# PCM-DAC.net
KiCad netlist of a schematic drawn in EAGLE
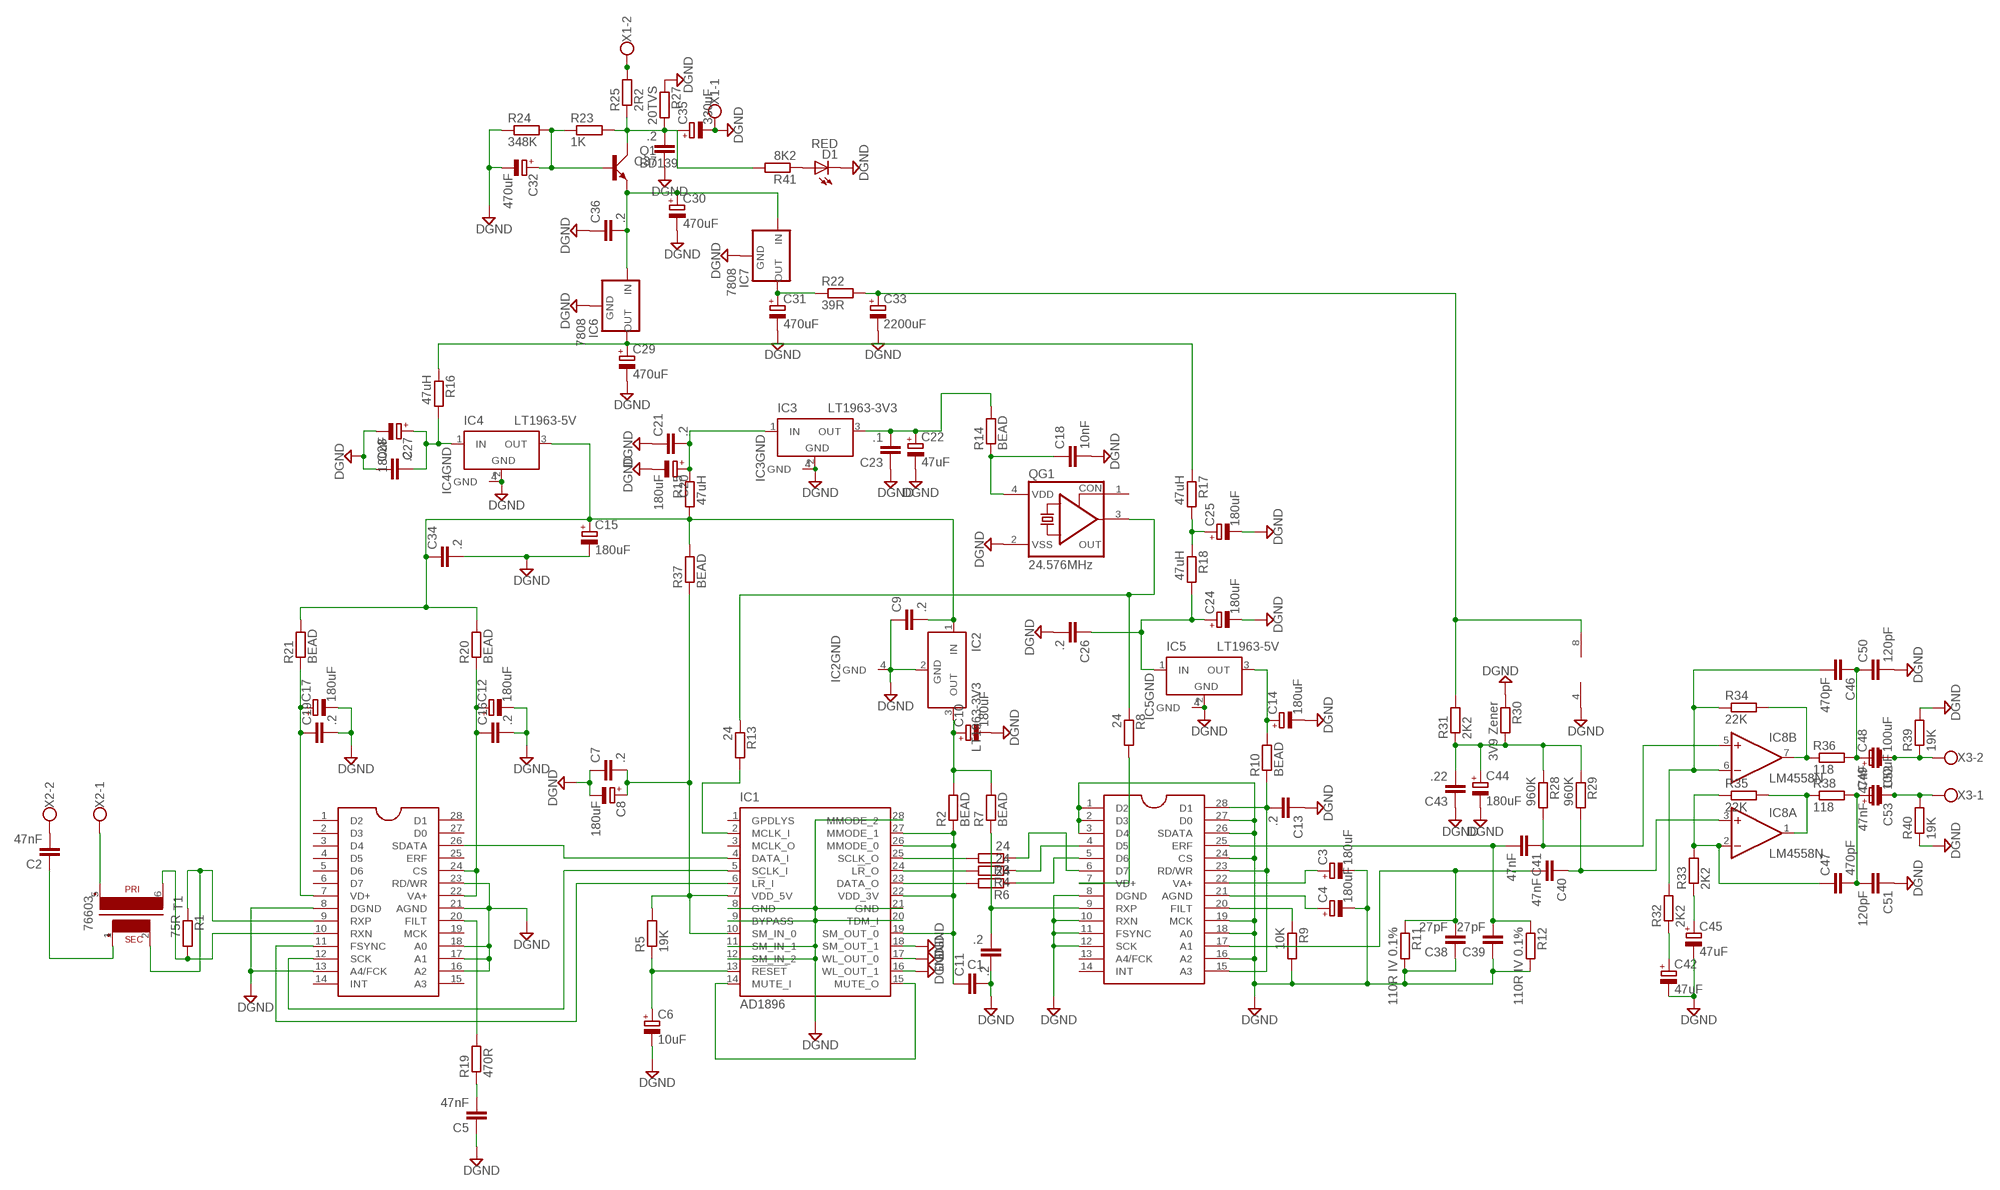
[diagram p0: schematic, sheet 1]

(export (version "E")
  (design (tool "Eeschema 10.0.6"))
  (components
    (comp (ref "C1")
      (value ".2")
      (footprint "eagle-import:C1210K")
      (libsource (lib "eagle-import") (part "C-EUC1210K"))
    )
    (comp (ref "C2")
      (value "47nF")
      (footprint "eagle-import:C050-075X075")
      (libsource (lib "eagle-import") (part "C-EU050-075X075"))
    )
    (comp (ref "C3")
      (value "180uF")
      (footprint "eagle-import:E3,5-8")
      (libsource (lib "eagle-import") (part "CPOL-EUE3.5-8"))
    )
    (comp (ref "C4")
      (value "180uF")
      (footprint "eagle-import:E3,5-8")
      (libsource (lib "eagle-import") (part "CPOL-EUE3.5-8"))
    )
    (comp (ref "C5")
      (value "47nF")
      (footprint "eagle-import:C050-075X075")
      (libsource (lib "eagle-import") (part "C-EU050-075X075"))
    )
    (comp (ref "C6")
      (value "10uF")
      (footprint "eagle-import:E2,5-7")
      (libsource (lib "eagle-import") (part "CPOL-EUE2.5-7"))
    )
    (comp (ref "C7")
      (value ".2")
      (footprint "eagle-import:C1210K")
      (libsource (lib "eagle-import") (part "C-EUC1210K"))
    )
    (comp (ref "C8")
      (value "180uF")
      (footprint "eagle-import:E3,5-8")
      (libsource (lib "eagle-import") (part "CPOL-EUE3.5-8"))
    )
    (comp (ref "C9")
      (value ".2")
      (footprint "eagle-import:C1210K")
      (libsource (lib "eagle-import") (part "C-EUC1210K"))
    )
    (comp (ref "C10")
      (value "180uF")
      (footprint "eagle-import:E3,5-8")
      (libsource (lib "eagle-import") (part "CPOL-EUE3.5-8"))
    )
    (comp (ref "C11")
      (value ".2")
      (footprint "eagle-import:C1210K")
      (libsource (lib "eagle-import") (part "C-EUC1210K"))
    )
    (comp (ref "C12")
      (value "180uF")
      (footprint "eagle-import:E3,5-8")
      (libsource (lib "eagle-import") (part "CPOL-EUE3.5-8"))
    )
    (comp (ref "C13")
      (value ".2")
      (footprint "eagle-import:C1210K")
      (libsource (lib "eagle-import") (part "C-EUC1210K"))
    )
    (comp (ref "C14")
      (value "180uF")
      (footprint "eagle-import:E3,5-8")
      (libsource (lib "eagle-import") (part "CPOL-EUE3.5-8"))
    )
    (comp (ref "C15")
      (value "180uF")
      (footprint "eagle-import:E3,5-8")
      (libsource (lib "eagle-import") (part "CPOL-EUE3.5-8"))
    )
    (comp (ref "C16")
      (value ".2")
      (footprint "eagle-import:C1210K")
      (libsource (lib "eagle-import") (part "C-EUC1210K"))
    )
    (comp (ref "C17")
      (value "180uF")
      (footprint "eagle-import:E3,5-8")
      (libsource (lib "eagle-import") (part "CPOL-EUE3.5-8"))
    )
    (comp (ref "C18")
      (value "10nF")
      (footprint "eagle-import:C1210K")
      (libsource (lib "eagle-import") (part "C-EUC1210K"))
    )
    (comp (ref "C19")
      (value ".2")
      (footprint "eagle-import:C1210K")
      (libsource (lib "eagle-import") (part "C-EUC1210K"))
    )
    (comp (ref "C20")
      (value "180uF")
      (footprint "eagle-import:E3,5-8")
      (libsource (lib "eagle-import") (part "CPOL-EUE3.5-8"))
    )
    (comp (ref "C21")
      (value ".2")
      (footprint "eagle-import:C1210K")
      (libsource (lib "eagle-import") (part "C-EUC1210K"))
    )
    (comp (ref "C22")
      (value "47uF")
      (footprint "eagle-import:E3,5-8")
      (libsource (lib "eagle-import") (part "CPOL-EUE3.5-8"))
    )
    (comp (ref "C23")
      (value ".1")
      (footprint "eagle-import:C1210K")
      (libsource (lib "eagle-import") (part "C-EUC1210K"))
    )
    (comp (ref "C24")
      (value "180uF")
      (footprint "eagle-import:E3,5-8")
      (libsource (lib "eagle-import") (part "CPOL-EUE3.5-8"))
    )
    (comp (ref "C25")
      (value "180uF")
      (footprint "eagle-import:E3,5-8")
      (libsource (lib "eagle-import") (part "CPOL-EUE3.5-8"))
    )
    (comp (ref "C26")
      (value ".2")
      (footprint "eagle-import:C1210K")
      (libsource (lib "eagle-import") (part "C-EUC1210K"))
    )
    (comp (ref "C27")
      (value "180uF")
      (footprint "eagle-import:E3,5-8")
      (libsource (lib "eagle-import") (part "CPOL-EUE3.5-8"))
    )
    (comp (ref "C28")
      (value ".2")
      (footprint "eagle-import:C1210K")
      (libsource (lib "eagle-import") (part "C-EUC1210K"))
    )
    (comp (ref "C29")
      (value "470uF")
      (footprint "eagle-import:E5-10,5")
      (libsource (lib "eagle-import") (part "CPOL-EUE5-10.5"))
    )
    (comp (ref "C30")
      (value "470uF")
      (footprint "eagle-import:E5-10,5")
      (libsource (lib "eagle-import") (part "CPOL-EUE5-10.5"))
    )
    (comp (ref "C31")
      (value "470uF")
      (footprint "eagle-import:E5-10,5")
      (libsource (lib "eagle-import") (part "CPOL-EUE5-10.5"))
    )
    (comp (ref "C32")
      (value "470uF")
      (footprint "eagle-import:E5-10,5")
      (libsource (lib "eagle-import") (part "CPOL-EUE5-10.5"))
    )
    (comp (ref "C33")
      (value "2200uF")
      (footprint "eagle-import:E7,5-16")
      (libsource (lib "eagle-import") (part "CPOL-EUE7.5-16"))
    )
    (comp (ref "C34")
      (value ".2")
      (footprint "eagle-import:C1210K")
      (libsource (lib "eagle-import") (part "C-EUC1210K"))
    )
    (comp (ref "C35")
      (value "330uF")
      (footprint "eagle-import:E7,5-16")
      (libsource (lib "eagle-import") (part "CPOL-EUE7.5-16"))
    )
    (comp (ref "C36")
      (value ".2")
      (footprint "eagle-import:C1210K")
      (libsource (lib "eagle-import") (part "C-EUC1210K"))
    )
    (comp (ref "C37")
      (value ".2")
      (footprint "eagle-import:C1210K")
      (libsource (lib "eagle-import") (part "C-EUC1210K"))
    )
    (comp (ref "C38")
      (value "27pF")
      (footprint "eagle-import:C1210K")
      (libsource (lib "eagle-import") (part "C-EUC1210K"))
    )
    (comp (ref "C39")
      (value "27pF")
      (footprint "eagle-import:C1210K")
      (libsource (lib "eagle-import") (part "C-EUC1210K"))
    )
    (comp (ref "C40")
      (value "47nF")
      (footprint "eagle-import:C050-075X075")
      (libsource (lib "eagle-import") (part "C-EU050-075X075"))
    )
    (comp (ref "C41")
      (value "47nF")
      (footprint "eagle-import:C050-075X075")
      (libsource (lib "eagle-import") (part "C-EU050-075X075"))
    )
    (comp (ref "C42")
      (value "47uF")
      (footprint "eagle-import:E3,5-8")
      (libsource (lib "eagle-import") (part "CPOL-EUE3.5-8"))
    )
    (comp (ref "C43")
      (value ".22")
      (footprint "eagle-import:C1210K")
      (libsource (lib "eagle-import") (part "C-EUC1210K"))
    )
    (comp (ref "C44")
      (value "180uF")
      (footprint "eagle-import:E5-10,5")
      (libsource (lib "eagle-import") (part "CPOL-EUE5-10.5"))
    )
    (comp (ref "C45")
      (value "47uF")
      (footprint "eagle-import:E3,5-8")
      (libsource (lib "eagle-import") (part "CPOL-EUE3.5-8"))
    )
    (comp (ref "C46")
      (value "470pF")
      (footprint "eagle-import:C1210K")
      (libsource (lib "eagle-import") (part "C-EUC1210K"))
    )
    (comp (ref "C47")
      (value "470pF")
      (footprint "eagle-import:C1210K")
      (libsource (lib "eagle-import") (part "C-EUC1210K"))
    )
    (comp (ref "C48")
      (value "100uF")
      (footprint "eagle-import:E5-10,5")
      (libsource (lib "eagle-import") (part "CPOL-EUE5-10.5"))
    )
    (comp (ref "C49")
      (value "100uF")
      (footprint "eagle-import:E5-10,5")
      (libsource (lib "eagle-import") (part "CPOL-EUE5-10.5"))
    )
    (comp (ref "C50")
      (value "120pF")
      (footprint "eagle-import:C1210K")
      (libsource (lib "eagle-import") (part "C-EUC1210K"))
    )
    (comp (ref "C51")
      (value "120pF")
      (footprint "eagle-import:C1210K")
      (libsource (lib "eagle-import") (part "C-EUC1210K"))
    )
    (comp (ref "C52")
      (value "47nF")
      (footprint "eagle-import:C050-075X075")
      (libsource (lib "eagle-import") (part "C-EU050-075X075"))
    )
    (comp (ref "C53")
      (value "47nF")
      (footprint "eagle-import:C050-075X075")
      (libsource (lib "eagle-import") (part "C-EU050-075X075"))
    )
    (comp (ref "D1")
      (value "RED")
      (footprint "eagle-import:SFH482")
      (libsource (lib "eagle-import") (part "SFH482"))
    )
    (comp (ref "IC1")
      (value "AD1896")
      (footprint "eagle-import:DIL28-6")
      (libsource (lib "eagle-import") (part "AD1896JN"))
    )
    (comp (ref "IC2")
      (value "LT1963-3V3")
      (footprint "eagle-import:SOT223")
      (libsource (lib "eagle-import") (part "LT1129CST5"))
    )
    (comp (ref "IC3")
      (value "LT1963-3V3")
      (footprint "eagle-import:SOT223")
      (libsource (lib "eagle-import") (part "LT1129CST5"))
    )
    (comp (ref "IC4")
      (value "LT1963-5V")
      (footprint "eagle-import:SOT223")
      (libsource (lib "eagle-import") (part "LT1129CST5"))
    )
    (comp (ref "IC5")
      (value "LT1963-5V")
      (footprint "eagle-import:SOT223")
      (libsource (lib "eagle-import") (part "LT1129CST5"))
    )
    (comp (ref "IC6")
      (value "7808")
      (footprint "eagle-import:78XXL")
      (libsource (lib "eagle-import") (part "78XXL"))
    )
    (comp (ref "IC7")
      (value "7808")
      (footprint "eagle-import:78XXL")
      (libsource (lib "eagle-import") (part "78XXL"))
    )
    (comp (ref "IC8")
      (value "LM4558N")
      (footprint "eagle-import:DIL08")
      (libsource (lib "eagle-import") (part "4558NLM"))
    )
    (comp (ref "Q1")
      (value "BD139")
      (footprint "eagle-import:TO126AV")
      (libsource (lib "eagle-import") (part "BD139"))
    )
    (comp (ref "QG1")
      (value "24.576MHz")
      (footprint "eagle-import:1100S")
      (libsource (lib "eagle-import") (part "CRYSTAL_RES-1100S"))
    )
    (comp (ref "R1")
      (value "75R")
      (footprint "eagle-import:0309_12")
      (libsource (lib "eagle-import") (part "R-EU_0309/12"))
    )
    (comp (ref "R2")
      (value "BEAD")
      (footprint "eagle-import:R1210")
      (libsource (lib "eagle-import") (part "R-EU_R1210"))
    )
    (comp (ref "R3")
      (value "24")
      (footprint "eagle-import:R1210")
      (libsource (lib "eagle-import") (part "R-EU_R1210"))
    )
    (comp (ref "R4")
      (value "24")
      (footprint "eagle-import:R1210")
      (libsource (lib "eagle-import") (part "R-EU_R1210"))
    )
    (comp (ref "R5")
      (value "19K")
      (footprint "eagle-import:0204_7")
      (libsource (lib "eagle-import") (part "R-EU_0204/7"))
    )
    (comp (ref "R6")
      (value "24")
      (footprint "eagle-import:R1210")
      (libsource (lib "eagle-import") (part "R-EU_R1210"))
    )
    (comp (ref "R7")
      (value "BEAD")
      (footprint "eagle-import:R1210")
      (libsource (lib "eagle-import") (part "R-EU_R1210"))
    )
    (comp (ref "R8")
      (value "24")
      (footprint "eagle-import:R1210")
      (libsource (lib "eagle-import") (part "R-EU_R1210"))
    )
    (comp (ref "R9")
      (value "10K")
      (footprint "eagle-import:R1210")
      (libsource (lib "eagle-import") (part "R-EU_R1210"))
    )
    (comp (ref "R10")
      (value "BEAD")
      (footprint "eagle-import:R1210")
      (libsource (lib "eagle-import") (part "R-EU_R1210"))
    )
    (comp (ref "R11")
      (value "110R IV 0.1%")
      (footprint "eagle-import:0309_12")
      (libsource (lib "eagle-import") (part "R-EU_0309/12"))
    )
    (comp (ref "R12")
      (value "110R IV 0.1%")
      (footprint "eagle-import:0309_12")
      (libsource (lib "eagle-import") (part "R-EU_0309/12"))
    )
    (comp (ref "R13")
      (value "24")
      (footprint "eagle-import:R1210")
      (libsource (lib "eagle-import") (part "R-EU_R1210"))
    )
    (comp (ref "R14")
      (value "BEAD")
      (footprint "eagle-import:R1210")
      (libsource (lib "eagle-import") (part "R-EU_R1210"))
    )
    (comp (ref "R15")
      (value "47uH")
      (footprint "eagle-import:0309_12")
      (libsource (lib "eagle-import") (part "R-EU_0309/12"))
    )
    (comp (ref "R16")
      (value "47uH")
      (footprint "eagle-import:0309_12")
      (libsource (lib "eagle-import") (part "R-EU_0309/12"))
    )
    (comp (ref "R17")
      (value "47uH")
      (footprint "eagle-import:0309_12")
      (libsource (lib "eagle-import") (part "R-EU_0309/12"))
    )
    (comp (ref "R18")
      (value "47uH")
      (footprint "eagle-import:0309_12")
      (libsource (lib "eagle-import") (part "R-EU_0309/12"))
    )
    (comp (ref "R19")
      (value "470R")
      (footprint "eagle-import:0204_7")
      (libsource (lib "eagle-import") (part "R-EU_0204/7"))
    )
    (comp (ref "R20")
      (value "BEAD")
      (footprint "eagle-import:R1210")
      (libsource (lib "eagle-import") (part "R-EU_R1210"))
    )
    (comp (ref "R21")
      (value "BEAD")
      (footprint "eagle-import:R1210")
      (libsource (lib "eagle-import") (part "R-EU_R1210"))
    )
    (comp (ref "R22")
      (value "39R")
      (footprint "eagle-import:0309_12")
      (libsource (lib "eagle-import") (part "R-EU_0309/12"))
    )
    (comp (ref "R23")
      (value "1K")
      (footprint "eagle-import:R1210")
      (libsource (lib "eagle-import") (part "R-EU_R1210"))
    )
    (comp (ref "R24")
      (value "348K")
      (footprint "eagle-import:R1210")
      (libsource (lib "eagle-import") (part "R-EU_R1210"))
    )
    (comp (ref "R25")
      (value "2R2")
      (footprint "eagle-import:0309_12")
      (libsource (lib "eagle-import") (part "R-EU_0309/12"))
    )
    (comp (ref "R27")
      (value "20TVS")
      (footprint "eagle-import:R5025")
      (libsource (lib "eagle-import") (part "R-EU_R5025"))
    )
    (comp (ref "R28")
      (value "960K")
      (footprint "eagle-import:0309_12")
      (libsource (lib "eagle-import") (part "R-EU_0309/12"))
    )
    (comp (ref "R29")
      (value "960K")
      (footprint "eagle-import:0309_12")
      (libsource (lib "eagle-import") (part "R-EU_0309/12"))
    )
    (comp (ref "R30")
      (value "3V9 Zener")
      (footprint "eagle-import:R1210")
      (libsource (lib "eagle-import") (part "R-EU_R1210"))
    )
    (comp (ref "R31")
      (value "2K2")
      (footprint "eagle-import:R1210")
      (libsource (lib "eagle-import") (part "R-EU_R1210"))
    )
    (comp (ref "R32")
      (value "2K2")
      (footprint "eagle-import:R1210")
      (libsource (lib "eagle-import") (part "R-EU_R1210"))
    )
    (comp (ref "R33")
      (value "2K2")
      (footprint "eagle-import:R1210")
      (libsource (lib "eagle-import") (part "R-EU_R1210"))
    )
    (comp (ref "R34")
      (value "22K")
      (footprint "eagle-import:0309_12")
      (libsource (lib "eagle-import") (part "R-EU_0309/12"))
    )
    (comp (ref "R35")
      (value "22K")
      (footprint "eagle-import:0309_12")
      (libsource (lib "eagle-import") (part "R-EU_0309/12"))
    )
    (comp (ref "R36")
      (value "118")
      (footprint "eagle-import:0309_12")
      (libsource (lib "eagle-import") (part "R-EU_0309/12"))
    )
    (comp (ref "R37")
      (value "BEAD")
      (footprint "eagle-import:R1210")
      (libsource (lib "eagle-import") (part "R-EU_R1210"))
    )
    (comp (ref "R38")
      (value "118")
      (footprint "eagle-import:0309_12")
      (libsource (lib "eagle-import") (part "R-EU_0309/12"))
    )
    (comp (ref "R39")
      (value "19K")
      (footprint "eagle-import:0309_12")
      (libsource (lib "eagle-import") (part "R-EU_0309/12"))
    )
    (comp (ref "R40")
      (value "19K")
      (footprint "eagle-import:0309_12")
      (libsource (lib "eagle-import") (part "R-EU_0309/12"))
    )
    (comp (ref "R41")
      (value "8K2")
      (footprint "eagle-import:R1210")
      (libsource (lib "eagle-import") (part "R-EU_R1210"))
    )
    (comp (ref "T1")
      (value "76603")
      (footprint "eagle-import:766-4")
      (libsource (lib "eagle-import") (part "76603"))
    )
    (comp (ref "U$1")
      (value "CS8412")
      (footprint "eagle-import:DIL28")
      (libsource (lib "eagle-import") (part "CS8412DIP"))
    )
    (comp (ref "U$2")
      (value "PCM1794A")
      (footprint "eagle-import:DIL28")
      (libsource (lib "eagle-import") (part "CS8412DIP"))
    )
    (comp (ref "X1")
      (value "W237-02P")
      (footprint "eagle-import:W237-132")
      (libsource (lib "eagle-import") (part "W237-02P"))
    )
    (comp (ref "X2")
      (value "W237-02P")
      (footprint "eagle-import:W237-132")
      (libsource (lib "eagle-import") (part "W237-02P"))
    )
    (comp (ref "X3")
      (value "W237-02P")
      (footprint "eagle-import:W237-132")
      (libsource (lib "eagle-import") (part "W237-02P"))
    )
  )
  (nets
    (net (code "1") (name "DGND") (class "Default")
      (node (ref "C1") (pin "1") (pinfunction "1_1") (pintype "passive"))
      (node (ref "C10") (pin "-") (pinfunction "-_-") (pintype "passive"))
      (node (ref "C11") (pin "2") (pinfunction "2_2") (pintype "passive"))
      (node (ref "C12") (pin "-") (pinfunction "-_-") (pintype "passive"))
      (node (ref "C13") (pin "1") (pinfunction "1_1") (pintype "passive"))
      (node (ref "C14") (pin "-") (pinfunction "-_-") (pintype "passive"))
      (node (ref "C15") (pin "-") (pinfunction "-_-") (pintype "passive"))
      (node (ref "C16") (pin "2") (pinfunction "2_2") (pintype "passive"))
      (node (ref "C17") (pin "-") (pinfunction "-_-") (pintype "passive"))
      (node (ref "C18") (pin "2") (pinfunction "2_2") (pintype "passive"))
      (node (ref "C19") (pin "2") (pinfunction "2_2") (pintype "passive"))
      (node (ref "C20") (pin "-") (pinfunction "-_-") (pintype "passive"))
      (node (ref "C21") (pin "1") (pinfunction "1_1") (pintype "passive"))
      (node (ref "C22") (pin "-") (pinfunction "-_-") (pintype "passive"))
      (node (ref "C23") (pin "1") (pinfunction "1_1") (pintype "passive"))
      (node (ref "C24") (pin "-") (pinfunction "-_-") (pintype "passive"))
      (node (ref "C25") (pin "-") (pinfunction "-_-") (pintype "passive"))
      (node (ref "C26") (pin "2") (pinfunction "2_2") (pintype "passive"))
      (node (ref "C27") (pin "-") (pinfunction "-_-") (pintype "passive"))
      (node (ref "C28") (pin "1") (pinfunction "1_1") (pintype "passive"))
      (node (ref "C29") (pin "-") (pinfunction "-_-") (pintype "passive"))
      (node (ref "C3") (pin "-") (pinfunction "-_-") (pintype "passive"))
      (node (ref "C30") (pin "-") (pinfunction "-_-") (pintype "passive"))
      (node (ref "C31") (pin "-") (pinfunction "-_-") (pintype "passive"))
      (node (ref "C32") (pin "-") (pinfunction "-_-") (pintype "passive"))
      (node (ref "C33") (pin "-") (pinfunction "-_-") (pintype "passive"))
      (node (ref "C34") (pin "2") (pinfunction "2_2") (pintype "passive"))
      (node (ref "C35") (pin "-") (pinfunction "-_-") (pintype "passive"))
      (node (ref "C36") (pin "1") (pinfunction "1_1") (pintype "passive"))
      (node (ref "C37") (pin "1") (pinfunction "1_1") (pintype "passive"))
      (node (ref "C38") (pin "1") (pinfunction "1_1") (pintype "passive"))
      (node (ref "C39") (pin "1") (pinfunction "1_1") (pintype "passive"))
      (node (ref "C4") (pin "-") (pinfunction "-_-") (pintype "passive"))
      (node (ref "C42") (pin "-") (pinfunction "-_-") (pintype "passive"))
      (node (ref "C43") (pin "1") (pinfunction "1_1") (pintype "passive"))
      (node (ref "C44") (pin "-") (pinfunction "-_-") (pintype "passive"))
      (node (ref "C45") (pin "-") (pinfunction "-_-") (pintype "passive"))
      (node (ref "C5") (pin "1") (pinfunction "1_1") (pintype "passive"))
      (node (ref "C50") (pin "2") (pinfunction "2_2") (pintype "passive"))
      (node (ref "C51") (pin "1") (pinfunction "1_1") (pintype "passive"))
      (node (ref "C6") (pin "-") (pinfunction "-_-") (pintype "passive"))
      (node (ref "C7") (pin "1") (pinfunction "1_1") (pintype "passive"))
      (node (ref "C8") (pin "-") (pinfunction "-_-") (pintype "passive"))
      (node (ref "C9") (pin "1") (pinfunction "1_1") (pintype "passive"))
      (node (ref "D1") (pin "K") (pinfunction "C_K") (pintype "passive"))
      (node (ref "IC1") (pin "11") (pinfunction "SM_IN_1_11") (pintype "input"))
      (node (ref "IC1") (pin "12") (pinfunction "SM_IN_2_12") (pintype "input"))
      (node (ref "IC1") (pin "16") (pinfunction "WL_OUT_1_16") (pintype "output"))
      (node (ref "IC1") (pin "17") (pinfunction "WL_OUT_0_17") (pintype "output"))
      (node (ref "IC1") (pin "18") (pinfunction "SM_OUT_1_18") (pintype "output"))
      (node (ref "IC1") (pin "20") (pinfunction "TDM_I_20") (pintype "input"))
      (node (ref "IC1") (pin "21") (pinfunction "GND_21") (pintype "power_in"))
      (node (ref "IC1") (pin "28") (pinfunction "MMODE_2_28") (pintype "input"))
      (node (ref "IC1") (pin "8") (pinfunction "GND_8") (pintype "power_in"))
      (node (ref "IC1") (pin "9") (pinfunction "BYPASS_9") (pintype "bidirectional"))
      (node (ref "IC2") (pin "2") (pinfunction "GND_2") (pintype "power_in"))
      (node (ref "IC2") (pin "4") (pinfunction "GND_4") (pintype "power_in"))
      (node (ref "IC3") (pin "2") (pinfunction "GND_2") (pintype "power_in"))
      (node (ref "IC3") (pin "4") (pinfunction "GND_4") (pintype "power_in"))
      (node (ref "IC4") (pin "2") (pinfunction "GND_2") (pintype "power_in"))
      (node (ref "IC4") (pin "4") (pinfunction "GND_4") (pintype "power_in"))
      (node (ref "IC5") (pin "2") (pinfunction "GND_2") (pintype "power_in"))
      (node (ref "IC5") (pin "4") (pinfunction "GND_4") (pintype "power_in"))
      (node (ref "IC6") (pin "GND") (pinfunction "GND_GND") (pintype "input"))
      (node (ref "IC7") (pin "GND") (pinfunction "GND_GND") (pintype "input"))
      (node (ref "IC8") (pin "4") (pinfunction "V-_4") (pintype "power_in"))
      (node (ref "QG1") (pin "2") (pinfunction "VSS_2") (pintype "power_in"))
      (node (ref "R11") (pin "2") (pinfunction "2_2") (pintype "passive"))
      (node (ref "R12") (pin "2") (pinfunction "2_2") (pintype "passive"))
      (node (ref "R24") (pin "1") (pinfunction "1_1") (pintype "passive"))
      (node (ref "R27") (pin "1") (pinfunction "1_1") (pintype "passive"))
      (node (ref "R30") (pin "1") (pinfunction "1_1") (pintype "passive"))
      (node (ref "R39") (pin "2") (pinfunction "2_2") (pintype "passive"))
      (node (ref "R40") (pin "1") (pinfunction "1_1") (pintype "passive"))
      (node (ref "R9") (pin "2") (pinfunction "2_2") (pintype "passive"))
      (node (ref "U$1") (pin "13") (pinfunction "A4/FCK_13") (pintype "bidirectional"))
      (node (ref "U$1") (pin "16") (pinfunction "A2_16") (pintype "bidirectional"))
      (node (ref "U$1") (pin "17") (pinfunction "A1_17") (pintype "bidirectional"))
      (node (ref "U$1") (pin "18") (pinfunction "A0_18") (pintype "bidirectional"))
      (node (ref "U$1") (pin "21") (pinfunction "AGND_21") (pintype "bidirectional"))
      (node (ref "U$1") (pin "23") (pinfunction "RD/WR_23") (pintype "bidirectional"))
      (node (ref "U$1") (pin "8") (pinfunction "DGND_8") (pintype "bidirectional"))
      (node (ref "U$2") (pin "1") (pinfunction "D2_1") (pintype "bidirectional"))
      (node (ref "U$2") (pin "10") (pinfunction "RXN_10") (pintype "bidirectional"))
      (node (ref "U$2") (pin "11") (pinfunction "FSYNC_11") (pintype "bidirectional"))
      (node (ref "U$2") (pin "12") (pinfunction "SCK_12") (pintype "bidirectional"))
      (node (ref "U$2") (pin "16") (pinfunction "A2_16") (pintype "bidirectional"))
      (node (ref "U$2") (pin "18") (pinfunction "A0_18") (pintype "bidirectional"))
      (node (ref "U$2") (pin "19") (pinfunction "MCK_19") (pintype "bidirectional"))
      (node (ref "U$2") (pin "2") (pinfunction "D3_2") (pintype "bidirectional"))
      (node (ref "U$2") (pin "24") (pinfunction "CS_24") (pintype "bidirectional"))
      (node (ref "U$2") (pin "26") (pinfunction "SDATA_26") (pintype "bidirectional"))
      (node (ref "U$2") (pin "27") (pinfunction "D0_27") (pintype "bidirectional"))
      (node (ref "U$2") (pin "3") (pinfunction "D4_3") (pintype "bidirectional"))
      (node (ref "U$2") (pin "8") (pinfunction "DGND_8") (pintype "bidirectional"))
      (node (ref "X1") (pin "1") (pinfunction "KL_1") (pintype "passive"))
    )
    (net (code "2") (name "Net-(C5-Pad2)") (class "Default")
      (node (ref "C5") (pin "2") (pinfunction "2_2") (pintype "passive"))
      (node (ref "R19") (pin "1") (pinfunction "1_1") (pintype "passive"))
    )
    (net (code "3") (name "Net-(C25-Pad+)") (class "Default")
      (node (ref "C25") (pin "+") (pinfunction "+_+") (pintype "passive"))
      (node (ref "R17") (pin "2") (pinfunction "2_2") (pintype "passive"))
      (node (ref "R18") (pin "1") (pinfunction "1_1") (pintype "passive"))
    )
    (net (code "4") (name "Net-(C29-Pad+)") (class "Default")
      (node (ref "C29") (pin "+") (pinfunction "+_+") (pintype "passive"))
      (node (ref "IC6") (pin "OUT") (pinfunction "OUT_OUT") (pintype "passive"))
      (node (ref "R16") (pin "1") (pinfunction "1_1") (pintype "passive"))
      (node (ref "R17") (pin "1") (pinfunction "1_1") (pintype "passive"))
    )
    (net (code "5") (name "Net-(C30-Pad+)") (class "Default")
      (node (ref "C30") (pin "+") (pinfunction "+_+") (pintype "passive"))
      (node (ref "C36") (pin "2") (pinfunction "2_2") (pintype "passive"))
      (node (ref "IC6") (pin "IN") (pinfunction "IN_IN") (pintype "input"))
      (node (ref "IC7") (pin "IN") (pinfunction "IN_IN") (pintype "input"))
      (node (ref "Q1") (pin "E") (pinfunction "E_E") (pintype "passive"))
    )
    (net (code "6") (name "Net-(C31-Pad+)") (class "Default")
      (node (ref "C31") (pin "+") (pinfunction "+_+") (pintype "passive"))
      (node (ref "IC7") (pin "OUT") (pinfunction "OUT_OUT") (pintype "passive"))
      (node (ref "R22") (pin "1") (pinfunction "1_1") (pintype "passive"))
    )
    (net (code "7") (name "Net-(C32-Pad+)") (class "Default")
      (node (ref "C32") (pin "+") (pinfunction "+_+") (pintype "passive"))
      (node (ref "Q1") (pin "B") (pinfunction "B_B") (pintype "passive"))
      (node (ref "R23") (pin "1") (pinfunction "1_1") (pintype "passive"))
      (node (ref "R24") (pin "2") (pinfunction "2_2") (pintype "passive"))
    )
    (net (code "8") (name "Net-(C35-Pad+)") (class "Default")
      (node (ref "C35") (pin "+") (pinfunction "+_+") (pintype "passive"))
      (node (ref "C37") (pin "2") (pinfunction "2_2") (pintype "passive"))
      (node (ref "Q1") (pin "C") (pinfunction "C_C") (pintype "passive"))
      (node (ref "R23") (pin "2") (pinfunction "2_2") (pintype "passive"))
      (node (ref "R25") (pin "1") (pinfunction "1_1") (pintype "passive"))
      (node (ref "R27") (pin "2") (pinfunction "2_2") (pintype "passive"))
      (node (ref "R41") (pin "2") (pinfunction "2_2") (pintype "passive"))
    )
    (net (code "9") (name "Net-(C42-Pad+)") (class "Default")
      (node (ref "C42") (pin "+") (pinfunction "+_+") (pintype "passive"))
      (node (ref "R32") (pin "1") (pinfunction "1_1") (pintype "passive"))
    )
    (net (code "10") (name "Net-(C43-Pad2)") (class "Default")
      (node (ref "C43") (pin "2") (pinfunction "2_2") (pintype "passive"))
      (node (ref "C44") (pin "+") (pinfunction "+_+") (pintype "passive"))
      (node (ref "R28") (pin "1") (pinfunction "1_1") (pintype "passive"))
      (node (ref "R29") (pin "1") (pinfunction "1_1") (pintype "passive"))
      (node (ref "R30") (pin "2") (pinfunction "2_2") (pintype "passive"))
      (node (ref "R31") (pin "1") (pinfunction "1_1") (pintype "passive"))
    )
    (net (code "11") (name "Net-(C45-Pad+)") (class "Default")
      (node (ref "C45") (pin "+") (pinfunction "+_+") (pintype "passive"))
      (node (ref "R33") (pin "1") (pinfunction "1_1") (pintype "passive"))
    )
    (net (code "12") (name "Net-(C46-Pad1)") (class "Default")
      (node (ref "C46") (pin "1") (pinfunction "1_1") (pintype "passive"))
      (node (ref "C48") (pin "+") (pinfunction "+_+") (pintype "passive"))
      (node (ref "C50") (pin "1") (pinfunction "1_1") (pintype "passive"))
      (node (ref "C52") (pin "2") (pinfunction "2_2") (pintype "passive"))
      (node (ref "R36") (pin "2") (pinfunction "2_2") (pintype "passive"))
    )
    (net (code "13") (name "Net-(C47-Pad2)") (class "Default")
      (node (ref "C47") (pin "2") (pinfunction "2_2") (pintype "passive"))
      (node (ref "C49") (pin "+") (pinfunction "+_+") (pintype "passive"))
      (node (ref "C51") (pin "2") (pinfunction "2_2") (pintype "passive"))
      (node (ref "C53") (pin "2") (pinfunction "2_2") (pintype "passive"))
      (node (ref "R38") (pin "2") (pinfunction "2_2") (pintype "passive"))
    )
    (net (code "14") (name "Net-(D1-PadA)") (class "Default")
      (node (ref "D1") (pin "A") (pinfunction "A_A") (pintype "passive"))
      (node (ref "R41") (pin "1") (pinfunction "1_1") (pintype "passive"))
    )
    (net (code "15") (name "Net-(IC1-DATA_I)") (class "Default")
      (node (ref "IC1") (pin "4") (pinfunction "DATA_I_4") (pintype "input"))
      (node (ref "U$1") (pin "26") (pinfunction "SDATA_26") (pintype "bidirectional"))
    )
    (net (code "16") (name "Net-(IC1-DATA_O)") (class "Default")
      (node (ref "IC1") (pin "23") (pinfunction "DATA_O_23") (pintype "output"))
      (node (ref "R6") (pin "2") (pinfunction "2_2") (pintype "passive"))
    )
    (net (code "17") (name "Net-(IC1-L~{R}_I)") (class "Default")
      (node (ref "IC1") (pin "6") (pinfunction "L~{R}_I_6") (pintype "input"))
      (node (ref "U$1") (pin "11") (pinfunction "FSYNC_11") (pintype "bidirectional"))
    )
    (net (code "18") (name "Net-(IC1-L~{R}_O)") (class "Default")
      (node (ref "IC1") (pin "24") (pinfunction "L~{R}_O_24") (pintype "input"))
      (node (ref "R4") (pin "2") (pinfunction "2_2") (pintype "passive"))
    )
    (net (code "19") (name "Net-(IC1-MCLK_I)") (class "Default")
      (node (ref "IC1") (pin "2") (pinfunction "MCLK_I_2") (pintype "input"))
      (node (ref "R13") (pin "2") (pinfunction "2_2") (pintype "passive"))
    )
    (net (code "20") (name "Net-(IC1-MMODE_0)") (class "Default")
      (node (ref "C11") (pin "1") (pinfunction "1_1") (pintype "passive"))
      (node (ref "IC1") (pin "19") (pinfunction "SM_OUT_0_19") (pintype "output"))
      (node (ref "IC1") (pin "22") (pinfunction "VDD_3V_22") (pintype "power_in"))
      (node (ref "IC1") (pin "26") (pinfunction "MMODE_0_26") (pintype "input"))
      (node (ref "IC1") (pin "27") (pinfunction "MMODE_1_27") (pintype "input"))
      (node (ref "R2") (pin "1") (pinfunction "1_1") (pintype "passive"))
    )
    (net (code "21") (name "Net-(IC1-MUTE_I)") (class "Default")
      (node (ref "IC1") (pin "14") (pinfunction "MUTE_I_14") (pintype "input"))
      (node (ref "IC1") (pin "15") (pinfunction "MUTE_O_15") (pintype "input"))
    )
    (net (code "22") (name "Net-(IC1-SCLK_I)") (class "Default")
      (node (ref "IC1") (pin "5") (pinfunction "SCLK_I_5") (pintype "input"))
      (node (ref "U$1") (pin "12") (pinfunction "SCK_12") (pintype "bidirectional"))
    )
    (net (code "23") (name "Net-(IC1-SCLK_O)") (class "Default")
      (node (ref "IC1") (pin "25") (pinfunction "SCLK_O_25") (pintype "output"))
      (node (ref "R3") (pin "2") (pinfunction "2_2") (pintype "passive"))
    )
    (net (code "24") (name "Net-(IC1-SM_IN_0)") (class "Default")
      (node (ref "C7") (pin "2") (pinfunction "2_2") (pintype "passive"))
      (node (ref "C8") (pin "+") (pinfunction "+_+") (pintype "passive"))
      (node (ref "IC1") (pin "10") (pinfunction "SM_IN_0_10") (pintype "input"))
      (node (ref "IC1") (pin "7") (pinfunction "VDD_5V_7") (pintype "power_in"))
      (node (ref "R37") (pin "1") (pinfunction "1_1") (pintype "passive"))
      (node (ref "R5") (pin "2") (pinfunction "2_2") (pintype "passive"))
    )
    (net (code "25") (name "Net-(IC1-~{RESET})") (class "Default")
      (node (ref "C6") (pin "+") (pinfunction "+_+") (pintype "passive"))
      (node (ref "IC1") (pin "13") (pinfunction "~{RESET}_13") (pintype "input"))
      (node (ref "R5") (pin "1") (pinfunction "1_1") (pintype "passive"))
    )
    (net (code "26") (name "Net-(IC2A-IN)") (class "Default")
      (node (ref "C15") (pin "+") (pinfunction "+_+") (pintype "passive"))
      (node (ref "C34") (pin "1") (pinfunction "1_1") (pintype "passive"))
      (node (ref "C9") (pin "2") (pinfunction "2_2") (pintype "passive"))
      (node (ref "IC2") (pin "1") (pinfunction "IN_1") (pintype "input"))
      (node (ref "IC4") (pin "3") (pinfunction "OUT_3") (pintype "output"))
      (node (ref "R15") (pin "2") (pinfunction "2_2") (pintype "passive"))
      (node (ref "R20") (pin "2") (pinfunction "2_2") (pintype "passive"))
      (node (ref "R21") (pin "2") (pinfunction "2_2") (pintype "passive"))
      (node (ref "R37") (pin "2") (pinfunction "2_2") (pintype "passive"))
    )
    (net (code "27") (name "Net-(IC2A-OUT)") (class "Default")
      (node (ref "C10") (pin "+") (pinfunction "+_+") (pintype "passive"))
      (node (ref "IC2") (pin "3") (pinfunction "OUT_3") (pintype "output"))
      (node (ref "R2") (pin "2") (pinfunction "2_2") (pintype "passive"))
      (node (ref "R7") (pin "2") (pinfunction "2_2") (pintype "passive"))
    )
    (net (code "28") (name "Net-(IC3A-IN)") (class "Default")
      (node (ref "C20") (pin "+") (pinfunction "+_+") (pintype "passive"))
      (node (ref "C21") (pin "2") (pinfunction "2_2") (pintype "passive"))
      (node (ref "IC3") (pin "1") (pinfunction "IN_1") (pintype "input"))
      (node (ref "R15") (pin "1") (pinfunction "1_1") (pintype "passive"))
    )
    (net (code "29") (name "Net-(IC3A-OUT)") (class "Default")
      (node (ref "C22") (pin "+") (pinfunction "+_+") (pintype "passive"))
      (node (ref "C23") (pin "2") (pinfunction "2_2") (pintype "passive"))
      (node (ref "IC3") (pin "3") (pinfunction "OUT_3") (pintype "output"))
      (node (ref "R14") (pin "2") (pinfunction "2_2") (pintype "passive"))
    )
    (net (code "30") (name "Net-(IC4A-IN)") (class "Default")
      (node (ref "C27") (pin "+") (pinfunction "+_+") (pintype "passive"))
      (node (ref "C28") (pin "2") (pinfunction "2_2") (pintype "passive"))
      (node (ref "IC4") (pin "1") (pinfunction "IN_1") (pintype "input"))
      (node (ref "R16") (pin "2") (pinfunction "2_2") (pintype "passive"))
    )
    (net (code "31") (name "Net-(IC5A-IN)") (class "Default")
      (node (ref "C24") (pin "+") (pinfunction "+_+") (pintype "passive"))
      (node (ref "C26") (pin "1") (pinfunction "1_1") (pintype "passive"))
      (node (ref "IC5") (pin "1") (pinfunction "IN_1") (pintype "input"))
      (node (ref "R18") (pin "2") (pinfunction "2_2") (pintype "passive"))
    )
    (net (code "32") (name "Net-(IC5A-OUT)") (class "Default")
      (node (ref "C14") (pin "+") (pinfunction "+_+") (pintype "passive"))
      (node (ref "IC5") (pin "3") (pinfunction "OUT_3") (pintype "output"))
      (node (ref "R10") (pin "2") (pinfunction "2_2") (pintype "passive"))
    )
    (net (code "33") (name "Net-(IC8A-+IN)") (class "Default")
      (node (ref "C40") (pin "1") (pinfunction "1_1") (pintype "passive"))
      (node (ref "IC8") (pin "3") (pinfunction "+IN_3") (pintype "input"))
      (node (ref "R29") (pin "2") (pinfunction "2_2") (pintype "passive"))
    )
    (net (code "34") (name "Net-(IC8A--IN)") (class "Default")
      (node (ref "C47") (pin "1") (pinfunction "1_1") (pintype "passive"))
      (node (ref "IC8") (pin "2") (pinfunction "-IN_2") (pintype "input"))
      (node (ref "R33") (pin "2") (pinfunction "2_2") (pintype "passive"))
      (node (ref "R35") (pin "1") (pinfunction "1_1") (pintype "passive"))
    )
    (net (code "35") (name "Net-(IC8A-OUT)") (class "Default")
      (node (ref "IC8") (pin "1") (pinfunction "OUT_1") (pintype "output"))
      (node (ref "R35") (pin "2") (pinfunction "2_2") (pintype "passive"))
      (node (ref "R38") (pin "1") (pinfunction "1_1") (pintype "passive"))
    )
    (net (code "36") (name "Net-(IC8B-+IN)") (class "Default")
      (node (ref "C41") (pin "1") (pinfunction "1_1") (pintype "passive"))
      (node (ref "IC8") (pin "5") (pinfunction "+IN_5") (pintype "input"))
      (node (ref "R28") (pin "2") (pinfunction "2_2") (pintype "passive"))
    )
    (net (code "37") (name "Net-(IC8B--IN)") (class "Default")
      (node (ref "C46") (pin "2") (pinfunction "2_2") (pintype "passive"))
      (node (ref "IC8") (pin "6") (pinfunction "-IN_6") (pintype "input"))
      (node (ref "R32") (pin "2") (pinfunction "2_2") (pintype "passive"))
      (node (ref "R34") (pin "1") (pinfunction "1_1") (pintype "passive"))
    )
    (net (code "38") (name "Net-(IC8B-OUT)") (class "Default")
      (node (ref "IC8") (pin "7") (pinfunction "OUT_7") (pintype "output"))
      (node (ref "R34") (pin "2") (pinfunction "2_2") (pintype "passive"))
      (node (ref "R36") (pin "1") (pinfunction "1_1") (pintype "passive"))
    )
    (net (code "39") (name "Net-(IC8C-V+)") (class "Default")
      (node (ref "C33") (pin "+") (pinfunction "+_+") (pintype "passive"))
      (node (ref "IC8") (pin "8") (pinfunction "V+_8") (pintype "power_in"))
      (node (ref "R22") (pin "2") (pinfunction "2_2") (pintype "passive"))
      (node (ref "R31") (pin "2") (pinfunction "2_2") (pintype "passive"))
    )
    (net (code "40") (name "Net-(QG1-OUT)") (class "Default")
      (node (ref "QG1") (pin "3") (pinfunction "OUT_3") (pintype "output"))
      (node (ref "R13") (pin "1") (pinfunction "1_1") (pintype "passive"))
      (node (ref "R8") (pin "1") (pinfunction "1_1") (pintype "passive"))
    )
    (net (code "41") (name "Net-(QG1-VDD)") (class "Default")
      (node (ref "C18") (pin "1") (pinfunction "1_1") (pintype "passive"))
      (node (ref "QG1") (pin "4") (pinfunction "VDD_4") (pintype "power_in"))
      (node (ref "R14") (pin "1") (pinfunction "1_1") (pintype "passive"))
    )
    (net (code "42") (name "Net-(T1-P1)") (class "Default")
      (node (ref "T1") (pin "5") (pinfunction "P1_5") (pintype "passive"))
      (node (ref "X2") (pin "1") (pinfunction "KL_1") (pintype "passive"))
    )
    (net (code "43") (name "Net-(T1-P2)") (class "Default")
      (node (ref "R1") (pin "2") (pinfunction "2_2") (pintype "passive"))
      (node (ref "T1") (pin "6") (pinfunction "P2_6") (pintype "passive"))
      (node (ref "U$1") (pin "10") (pinfunction "RXN_10") (pintype "bidirectional"))
    )
    (net (code "44") (name "Net-(T1-S1)") (class "Default")
      (node (ref "C2") (pin "1") (pinfunction "1_1") (pintype "passive"))
      (node (ref "T1") (pin "1") (pinfunction "S1_1") (pintype "passive"))
    )
    (net (code "45") (name "Net-(T1-S2)") (class "Default")
      (node (ref "R1") (pin "1") (pinfunction "1_1") (pintype "passive"))
      (node (ref "T1") (pin "2") (pinfunction "S2_2") (pintype "passive"))
      (node (ref "U$1") (pin "9") (pinfunction "RXP_9") (pintype "bidirectional"))
    )
    (net (code "46") (name "Net-(U$1-CS)") (class "Default")
      (node (ref "C12") (pin "+") (pinfunction "+_+") (pintype "passive"))
      (node (ref "C16") (pin "1") (pinfunction "1_1") (pintype "passive"))
      (node (ref "R20") (pin "1") (pinfunction "1_1") (pintype "passive"))
      (node (ref "U$1") (pin "22") (pinfunction "VA+_22") (pintype "bidirectional"))
      (node (ref "U$1") (pin "24") (pinfunction "CS_24") (pintype "bidirectional"))
    )
    (net (code "47") (name "Net-(U$1-FILT)") (class "Default")
      (node (ref "R19") (pin "2") (pinfunction "2_2") (pintype "passive"))
      (node (ref "U$1") (pin "20") (pinfunction "FILT_20") (pintype "bidirectional"))
    )
    (net (code "48") (name "Net-(U$1-VD+)") (class "Default")
      (node (ref "C17") (pin "+") (pinfunction "+_+") (pintype "passive"))
      (node (ref "C19") (pin "1") (pinfunction "1_1") (pintype "passive"))
      (node (ref "R21") (pin "1") (pinfunction "1_1") (pintype "passive"))
      (node (ref "U$1") (pin "7") (pinfunction "VD+_7") (pintype "bidirectional"))
    )
    (net (code "49") (name "Net-(U$2-A1)") (class "Default")
      (node (ref "C38") (pin "2") (pinfunction "2_2") (pintype "passive"))
      (node (ref "C40") (pin "2") (pinfunction "2_2") (pintype "passive"))
      (node (ref "R11") (pin "1") (pinfunction "1_1") (pintype "passive"))
      (node (ref "U$2") (pin "17") (pinfunction "A1_17") (pintype "bidirectional"))
    )
    (net (code "50") (name "Net-(U$2-A3)") (class "Default")
      (node (ref "C13") (pin "2") (pinfunction "2_2") (pintype "passive"))
      (node (ref "R10") (pin "1") (pinfunction "1_1") (pintype "passive"))
      (node (ref "U$2") (pin "15") (pinfunction "A3_15") (pintype "bidirectional"))
      (node (ref "U$2") (pin "23") (pinfunction "RD/WR_23") (pintype "bidirectional"))
      (node (ref "U$2") (pin "28") (pinfunction "D1_28") (pintype "bidirectional"))
    )
    (net (code "51") (name "Net-(U$2-AGND)") (class "Default")
      (node (ref "C4") (pin "+") (pinfunction "+_+") (pintype "passive"))
      (node (ref "U$2") (pin "21") (pinfunction "AGND_21") (pintype "bidirectional"))
    )
    (net (code "52") (name "Net-(U$2-D5)") (class "Default")
      (node (ref "R4") (pin "1") (pinfunction "1_1") (pintype "passive"))
      (node (ref "U$2") (pin "4") (pinfunction "D5_4") (pintype "bidirectional"))
    )
    (net (code "53") (name "Net-(U$2-D6)") (class "Default")
      (node (ref "R6") (pin "1") (pinfunction "1_1") (pintype "passive"))
      (node (ref "U$2") (pin "5") (pinfunction "D6_5") (pintype "bidirectional"))
    )
    (net (code "54") (name "Net-(U$2-D7)") (class "Default")
      (node (ref "R3") (pin "1") (pinfunction "1_1") (pintype "passive"))
      (node (ref "U$2") (pin "6") (pinfunction "D7_6") (pintype "bidirectional"))
    )
    (net (code "55") (name "Net-(U$2-ERF)") (class "Default")
      (node (ref "C39") (pin "2") (pinfunction "2_2") (pintype "passive"))
      (node (ref "C41") (pin "2") (pinfunction "2_2") (pintype "passive"))
      (node (ref "R12") (pin "1") (pinfunction "1_1") (pintype "passive"))
      (node (ref "U$2") (pin "25") (pinfunction "ERF_25") (pintype "bidirectional"))
    )
    (net (code "56") (name "Net-(U$2-FILT)") (class "Default")
      (node (ref "R9") (pin "1") (pinfunction "1_1") (pintype "passive"))
      (node (ref "U$2") (pin "20") (pinfunction "FILT_20") (pintype "bidirectional"))
    )
    (net (code "57") (name "Net-(U$2-RXP)") (class "Default")
      (node (ref "C1") (pin "2") (pinfunction "2_2") (pintype "passive"))
      (node (ref "R7") (pin "1") (pinfunction "1_1") (pintype "passive"))
      (node (ref "U$2") (pin "9") (pinfunction "RXP_9") (pintype "bidirectional"))
    )
    (net (code "58") (name "Net-(U$2-VA+)") (class "Default")
      (node (ref "C3") (pin "+") (pinfunction "+_+") (pintype "passive"))
      (node (ref "U$2") (pin "22") (pinfunction "VA+_22") (pintype "bidirectional"))
    )
    (net (code "59") (name "Net-(U$2-VD+)") (class "Default")
      (node (ref "R8") (pin "2") (pinfunction "2_2") (pintype "passive"))
      (node (ref "U$2") (pin "7") (pinfunction "VD+_7") (pintype "bidirectional"))
    )
    (net (code "60") (name "Net-(X1B-KL)") (class "Default")
      (node (ref "R25") (pin "2") (pinfunction "2_2") (pintype "passive"))
      (node (ref "X1") (pin "2") (pinfunction "KL_2") (pintype "passive"))
    )
    (net (code "61") (name "Net-(X2B-KL)") (class "Default")
      (node (ref "C2") (pin "2") (pinfunction "2_2") (pintype "passive"))
      (node (ref "X2") (pin "2") (pinfunction "KL_2") (pintype "passive"))
    )
    (net (code "62") (name "Net-(X3A-KL)") (class "Default")
      (node (ref "C49") (pin "-") (pinfunction "-_-") (pintype "passive"))
      (node (ref "C53") (pin "1") (pinfunction "1_1") (pintype "passive"))
      (node (ref "R40") (pin "2") (pinfunction "2_2") (pintype "passive"))
      (node (ref "X3") (pin "1") (pinfunction "KL_1") (pintype "passive"))
    )
    (net (code "63") (name "Net-(X3B-KL)") (class "Default")
      (node (ref "C48") (pin "-") (pinfunction "-_-") (pintype "passive"))
      (node (ref "C52") (pin "1") (pinfunction "1_1") (pintype "passive"))
      (node (ref "R39") (pin "1") (pinfunction "1_1") (pintype "passive"))
      (node (ref "X3") (pin "2") (pinfunction "KL_2") (pintype "passive"))
    )
    (net (code "64") (name "unconnected-(IC1-GPDLYS-Pad1)") (class "Default")
      (node (ref "IC1") (pin "1") (pinfunction "GPDLYS_1") (pintype "input"))
    )
    (net (code "65") (name "unconnected-(IC1-MCLK_O-Pad3)") (class "Default")
      (node (ref "IC1") (pin "3") (pinfunction "MCLK_O_3") (pintype "output"))
    )
    (net (code "66") (name "unconnected-(QG1-CON-Pad1)") (class "Default")
      (node (ref "QG1") (pin "1") (pinfunction "CON_1") (pintype "input"))
    )
    (net (code "67") (name "unconnected-(U$1-A3-Pad15)") (class "Default")
      (node (ref "U$1") (pin "15") (pinfunction "A3_15") (pintype "bidirectional"))
    )
    (net (code "68") (name "unconnected-(U$1-D0-Pad27)") (class "Default")
      (node (ref "U$1") (pin "27") (pinfunction "D0_27") (pintype "bidirectional"))
    )
    (net (code "69") (name "unconnected-(U$1-D1-Pad28)") (class "Default")
      (node (ref "U$1") (pin "28") (pinfunction "D1_28") (pintype "bidirectional"))
    )
    (net (code "70") (name "unconnected-(U$1-D2-Pad1)") (class "Default")
      (node (ref "U$1") (pin "1") (pinfunction "D2_1") (pintype "bidirectional"))
    )
    (net (code "71") (name "unconnected-(U$1-D3-Pad2)") (class "Default")
      (node (ref "U$1") (pin "2") (pinfunction "D3_2") (pintype "bidirectional"))
    )
    (net (code "72") (name "unconnected-(U$1-D4-Pad3)") (class "Default")
      (node (ref "U$1") (pin "3") (pinfunction "D4_3") (pintype "bidirectional"))
    )
    (net (code "73") (name "unconnected-(U$1-D5-Pad4)") (class "Default")
      (node (ref "U$1") (pin "4") (pinfunction "D5_4") (pintype "bidirectional"))
    )
    (net (code "74") (name "unconnected-(U$1-D6-Pad5)") (class "Default")
      (node (ref "U$1") (pin "5") (pinfunction "D6_5") (pintype "bidirectional"))
    )
    (net (code "75") (name "unconnected-(U$1-D7-Pad6)") (class "Default")
      (node (ref "U$1") (pin "6") (pinfunction "D7_6") (pintype "bidirectional"))
    )
    (net (code "76") (name "unconnected-(U$1-ERF-Pad25)") (class "Default")
      (node (ref "U$1") (pin "25") (pinfunction "ERF_25") (pintype "bidirectional"))
    )
    (net (code "77") (name "unconnected-(U$1-INT-Pad14)") (class "Default")
      (node (ref "U$1") (pin "14") (pinfunction "INT_14") (pintype "bidirectional"))
    )
    (net (code "78") (name "unconnected-(U$1-MCK-Pad19)") (class "Default")
      (node (ref "U$1") (pin "19") (pinfunction "MCK_19") (pintype "bidirectional"))
    )
    (net (code "79") (name "unconnected-(U$2-A4{slash}FCK-Pad13)") (class "Default")
      (node (ref "U$2") (pin "13") (pinfunction "A4/FCK_13") (pintype "bidirectional"))
    )
    (net (code "80") (name "unconnected-(U$2-INT-Pad14)") (class "Default")
      (node (ref "U$2") (pin "14") (pinfunction "INT_14") (pintype "bidirectional"))
    )
  )
)
